# 1_P1_schdoc.net
KiCad netlist of a schematic drawn in Altium Designer
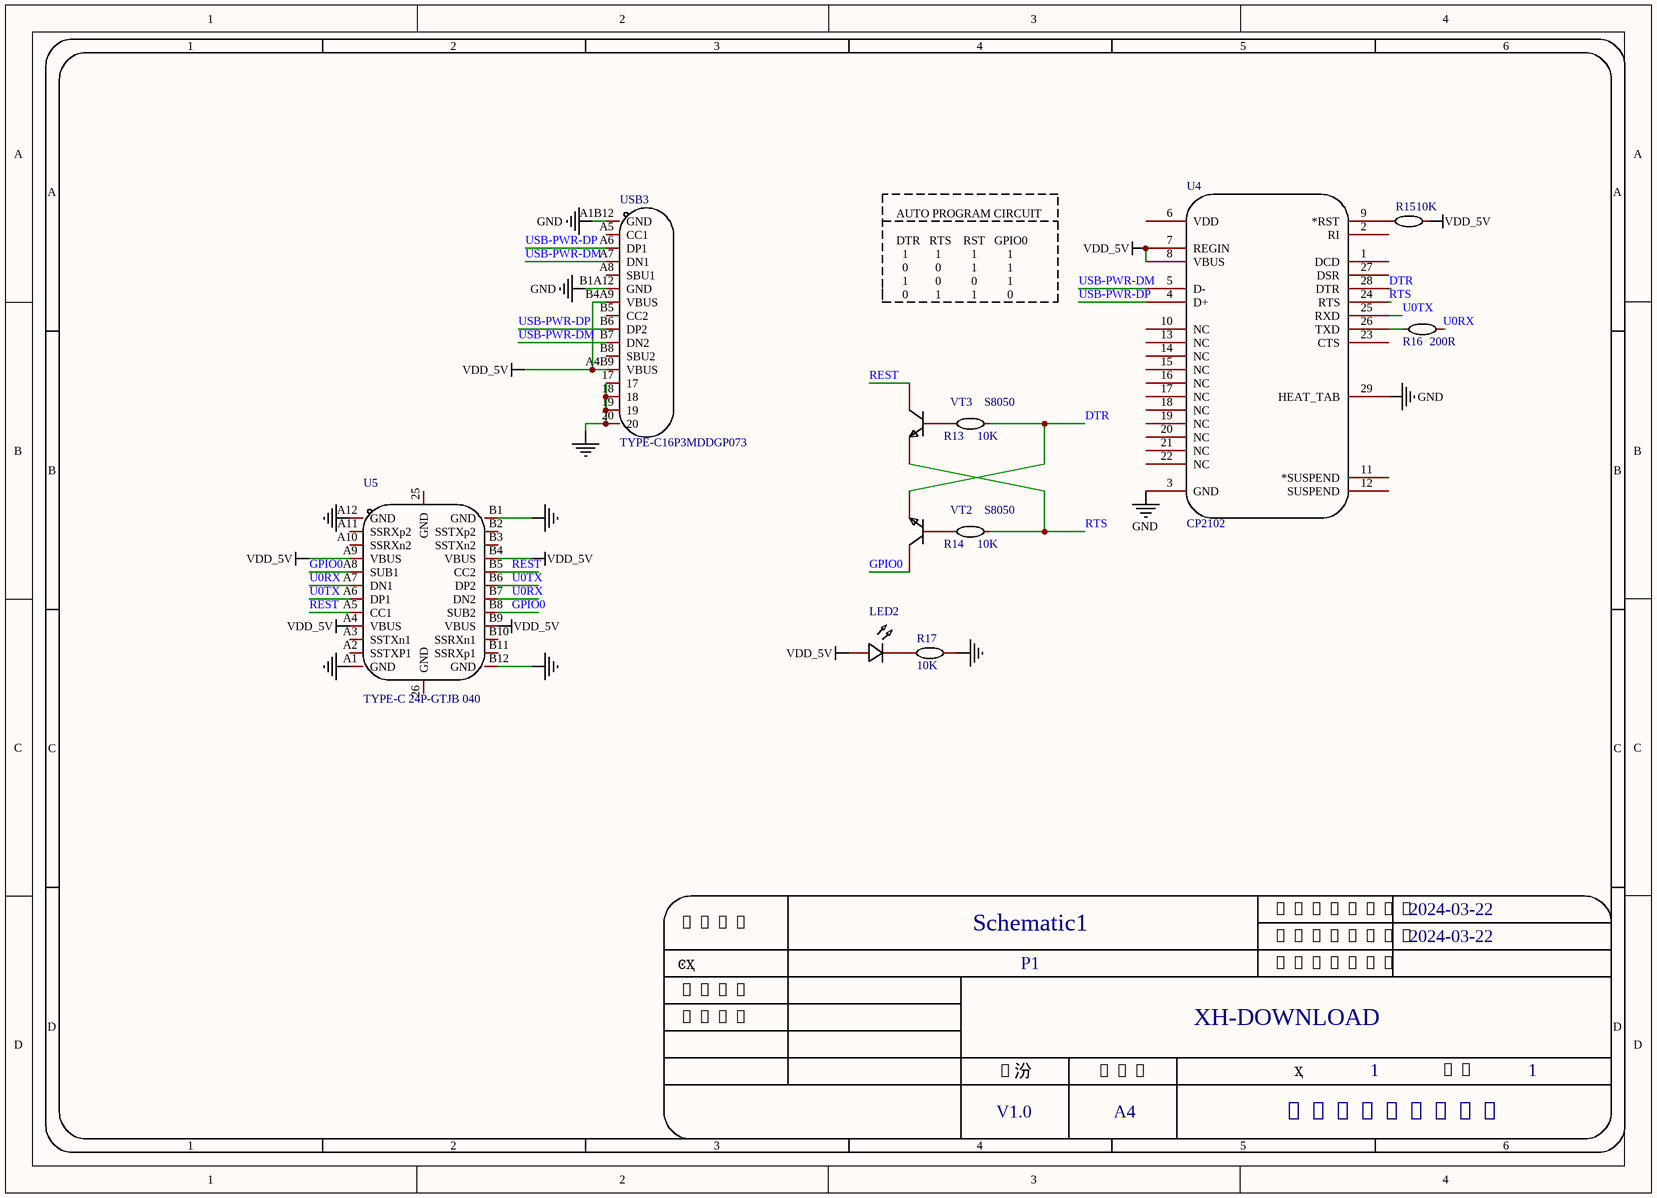
[diagram p0: 1_P1.schdoc.schdoc]

(export (version "E")
  (design (tool "Eeschema 10.0.6"))
  (components
    (comp (ref "LED2")
      (value "LED_0603-R")
      (footprint "LED_0603")
      (libsource (lib "altium-import") (part "root_0_LED_0603-R_"))
    )
    (comp (ref "R13")
      (value "10K")
      (footprint "C-0402")
      (description "Resistor")
      (fields (field (name "NAME") "10K"))
      (libsource (lib "altium-import") (part "root_2_12K_"))
    )
    (comp (ref "R14")
      (value "10K")
      (footprint "C-0402")
      (description "Resistor")
      (fields (field (name "NAME") "10K"))
      (libsource (lib "altium-import") (part "root_2_12K_"))
    )
    (comp (ref "R15")
      (value "10K")
      (footprint "C-0402")
      (description "Resistor")
      (fields (field (name "NAME") "10K"))
      (libsource (lib "altium-import") (part "root_2_10K_"))
    )
    (comp (ref "R16")
      (value "200R")
      (footprint "C-0402")
      (description "Resistor")
      (fields (field (name "NAME") "200R"))
      (libsource (lib "altium-import") (part "root_2_200R_"))
    )
    (comp (ref "R17")
      (value "10K")
      (footprint "R0603")
      (fields (field (name "NAME") "10K"))
      (libsource (lib "altium-import") (part "root_0_Res_0603_"))
    )
    (comp (ref "U4")
      (value "CP2102")
      (footprint "QFN28")
      (description "USB转TTL")
      (fields (field (name "NAME") "CP2102"))
      (libsource (lib "altium-import") (part "root_0_CP2102_"))
    )
    (comp (ref "U5")
      (value "TYPE-C 24P-GTJB 040")
      (footprint "USB-C-SMD_TYPE-C-24P-GTJB-040")
      (fields (field (name "NAME") "TYPE-C 24P-GTJB 040") (field (name "MANUFACTURER") "SHOU HAN(�׺�)"))
      (libsource (lib "altium-import") (part "root_0_TYPE-C 24P-GTJB 040_"))
    )
    (comp (ref "USB3")
      (value "TYPE-C16P3MDDGP073")
      (footprint "USB-SMD_TYPE-C16PIN-1")
      (fields (field (name "NAME") "TYPE-C16P3MDDGP073") (field (name "MANUFACTURER") "SHOU HAN(�׺�)"))
      (libsource (lib "altium-import") (part "root_0_TYPE-C16P3MDDGP073_"))
    )
    (comp (ref "VT2")
      (value "S8050")
      (footprint "SOT-233")
      (description "Surface mount NPN transistor, package SOT-23")
      (fields (field (name "NAME") "S8050"))
      (libsource (lib "altium-import") (part "root_2_S8050_"))
    )
    (comp (ref "VT3")
      (value "S8050")
      (footprint "SOT-233")
      (description "Surface mount NPN transistor, package SOT-23")
      (fields (field (name "NAME") "S8050"))
      (libsource (lib "altium-import") (part "root_0_mirrored_S8050_"))
    )
  )
  (nets
    (net (code "1") (name "/DTR") (class "Default")
      (node (ref "R13") (pin "1") (pinfunction "1_1") (pintype "passive"))
      (node (ref "U4") (pin "28") (pinfunction "DTR_28") (pintype "passive"))
      (node (ref "VT2") (pin "2") (pinfunction "E_2") (pintype "passive"))
    )
    (net (code "2") (name "/GPIO0") (class "Default")
      (node (ref "U5") (pin "A8") (pinfunction "SUB1_A8") (pintype "passive"))
      (node (ref "U5") (pin "B8") (pinfunction "SUB2_B8") (pintype "passive"))
      (node (ref "VT2") (pin "3") (pinfunction "C_3") (pintype "passive"))
    )
    (net (code "3") (name "/REST") (class "Default")
      (node (ref "U5") (pin "A5") (pinfunction "CC1_A5") (pintype "passive"))
      (node (ref "U5") (pin "B5") (pinfunction "CC2_B5") (pintype "passive"))
      (node (ref "VT3") (pin "3") (pinfunction "C_3") (pintype "passive"))
    )
    (net (code "4") (name "/RTS") (class "Default")
      (node (ref "R14") (pin "1") (pinfunction "1_1") (pintype "passive"))
      (node (ref "U4") (pin "24") (pinfunction "RTS_24") (pintype "passive"))
      (node (ref "VT3") (pin "2") (pinfunction "E_2") (pintype "passive"))
    )
    (net (code "5") (name "/U0RX") (class "Default")
      (node (ref "R16") (pin "1") (pinfunction "1_1") (pintype "passive"))
      (node (ref "U5") (pin "A7") (pinfunction "DN1_A7") (pintype "passive"))
      (node (ref "U5") (pin "B7") (pinfunction "DN2_B7") (pintype "passive"))
    )
    (net (code "6") (name "/U0TX") (class "Default")
      (node (ref "U4") (pin "25") (pinfunction "RXD_25") (pintype "passive"))
      (node (ref "U5") (pin "A6") (pinfunction "DP1_A6") (pintype "passive"))
      (node (ref "U5") (pin "B6") (pinfunction "DP2_B6") (pintype "passive"))
    )
    (net (code "7") (name "/USB-PWR-DM") (class "Default")
      (node (ref "U4") (pin "5") (pinfunction "D-_5") (pintype "passive"))
      (node (ref "USB3") (pin "A7") (pinfunction "DN1_A7") (pintype "passive"))
      (node (ref "USB3") (pin "B7") (pinfunction "DN2_B7") (pintype "passive"))
    )
    (net (code "8") (name "/USB-PWR-DP") (class "Default")
      (node (ref "U4") (pin "4") (pinfunction "D+_4") (pintype "passive"))
      (node (ref "USB3") (pin "A6") (pinfunction "DP1_A6") (pintype "passive"))
      (node (ref "USB3") (pin "B6") (pinfunction "DP2_B6") (pintype "passive"))
    )
    (net (code "9") (name "<NO NET>") (class "Default")
      (node (ref "R17") (pin "2") (pinfunction "2_2") (pintype "passive"))
      (node (ref "U5") (pin "A1") (pinfunction "GND_A1") (pintype "passive"))
      (node (ref "U5") (pin "A12") (pinfunction "GND_A12") (pintype "passive"))
      (node (ref "U5") (pin "B1") (pinfunction "GND_B1") (pintype "passive"))
      (node (ref "U5") (pin "B12") (pinfunction "GND_B12") (pintype "passive"))
    )
    (net (code "10") (name "GND") (class "Default")
      (node (ref "U4") (pin "29") (pinfunction "HEAT_TAB_29") (pintype "passive"))
      (node (ref "U4") (pin "3") (pinfunction "GND_3") (pintype "passive"))
      (node (ref "USB3") (pin "17") (pinfunction "17_17") (pintype "passive"))
      (node (ref "USB3") (pin "18") (pinfunction "18_18") (pintype "passive"))
      (node (ref "USB3") (pin "19") (pinfunction "19_19") (pintype "passive"))
      (node (ref "USB3") (pin "20") (pinfunction "20_20") (pintype "passive"))
      (node (ref "USB3") (pin "A1B12") (pinfunction "GND_A1B12") (pintype "passive"))
      (node (ref "USB3") (pin "B1A12") (pinfunction "GND_B1A12") (pintype "passive"))
    )
    (net (code "11") (name "Net-(LED2-C)") (class "Default")
      (node (ref "LED2") (pin "1") (pinfunction "C_1") (pintype "passive"))
      (node (ref "R17") (pin "1") (pinfunction "1_1") (pintype "passive"))
    )
    (net (code "12") (name "Net-(U4-*RST)") (class "Default")
      (node (ref "R15") (pin "2") (pinfunction "2_2") (pintype "passive"))
      (node (ref "U4") (pin "9") (pinfunction "*RST_9") (pintype "passive"))
    )
    (net (code "13") (name "Net-(U4-TXD)") (class "Default")
      (node (ref "R16") (pin "2") (pinfunction "2_2") (pintype "passive"))
      (node (ref "U4") (pin "26") (pinfunction "TXD_26") (pintype "passive"))
    )
    (net (code "14") (name "Net-(VT2-B)") (class "Default")
      (node (ref "R14") (pin "2") (pinfunction "2_2") (pintype "passive"))
      (node (ref "VT2") (pin "1") (pinfunction "B_1") (pintype "passive"))
    )
    (net (code "15") (name "Net-(VT3-B)") (class "Default")
      (node (ref "R13") (pin "2") (pinfunction "2_2") (pintype "passive"))
      (node (ref "VT3") (pin "1") (pinfunction "B_1") (pintype "passive"))
    )
    (net (code "16") (name "VDD_5V") (class "Default")
      (node (ref "LED2") (pin "2") (pinfunction "A_2") (pintype "passive"))
      (node (ref "R15") (pin "1") (pinfunction "1_1") (pintype "passive"))
      (node (ref "U4") (pin "7") (pinfunction "REGIN_7") (pintype "passive"))
      (node (ref "U4") (pin "8") (pinfunction "VBUS_8") (pintype "passive"))
      (node (ref "U5") (pin "A4") (pinfunction "VBUS_A4") (pintype "passive"))
      (node (ref "U5") (pin "A9") (pinfunction "VBUS_A9") (pintype "passive"))
      (node (ref "U5") (pin "B4") (pinfunction "VBUS_B4") (pintype "passive"))
      (node (ref "U5") (pin "B9") (pinfunction "VBUS_B9") (pintype "passive"))
      (node (ref "USB3") (pin "A4B9") (pinfunction "VBUS_A4B9") (pintype "passive"))
      (node (ref "USB3") (pin "B4A9") (pinfunction "VBUS_B4A9") (pintype "passive"))
    )
    (net (code "17") (name "unconnected-(U4-*SUSPEND-Pad11)") (class "Default")
      (node (ref "U4") (pin "11") (pinfunction "*SUSPEND_11") (pintype "passive"))
    )
    (net (code "18") (name "unconnected-(U4-CTS-Pad23)") (class "Default")
      (node (ref "U4") (pin "23") (pinfunction "CTS_23") (pintype "passive"))
    )
    (net (code "19") (name "unconnected-(U4-DCD-Pad1)") (class "Default")
      (node (ref "U4") (pin "1") (pinfunction "DCD_1") (pintype "passive"))
    )
    (net (code "20") (name "unconnected-(U4-DSR-Pad27)") (class "Default")
      (node (ref "U4") (pin "27") (pinfunction "DSR_27") (pintype "passive"))
    )
    (net (code "21") (name "unconnected-(U4-NC-Pad10)") (class "Default")
      (node (ref "U4") (pin "10") (pinfunction "NC_10") (pintype "passive"))
    )
    (net (code "22") (name "unconnected-(U4-NC-Pad13)") (class "Default")
      (node (ref "U4") (pin "13") (pinfunction "NC_13") (pintype "passive"))
    )
    (net (code "23") (name "unconnected-(U4-NC-Pad14)") (class "Default")
      (node (ref "U4") (pin "14") (pinfunction "NC_14") (pintype "passive"))
    )
    (net (code "24") (name "unconnected-(U4-NC-Pad15)") (class "Default")
      (node (ref "U4") (pin "15") (pinfunction "NC_15") (pintype "passive"))
    )
    (net (code "25") (name "unconnected-(U4-NC-Pad16)") (class "Default")
      (node (ref "U4") (pin "16") (pinfunction "NC_16") (pintype "passive"))
    )
    (net (code "26") (name "unconnected-(U4-NC-Pad17)") (class "Default")
      (node (ref "U4") (pin "17") (pinfunction "NC_17") (pintype "passive"))
    )
    (net (code "27") (name "unconnected-(U4-NC-Pad18)") (class "Default")
      (node (ref "U4") (pin "18") (pinfunction "NC_18") (pintype "passive"))
    )
    (net (code "28") (name "unconnected-(U4-NC-Pad19)") (class "Default")
      (node (ref "U4") (pin "19") (pinfunction "NC_19") (pintype "passive"))
    )
    (net (code "29") (name "unconnected-(U4-NC-Pad20)") (class "Default")
      (node (ref "U4") (pin "20") (pinfunction "NC_20") (pintype "passive"))
    )
    (net (code "30") (name "unconnected-(U4-NC-Pad21)") (class "Default")
      (node (ref "U4") (pin "21") (pinfunction "NC_21") (pintype "passive"))
    )
    (net (code "31") (name "unconnected-(U4-NC-Pad22)") (class "Default")
      (node (ref "U4") (pin "22") (pinfunction "NC_22") (pintype "passive"))
    )
    (net (code "32") (name "unconnected-(U4-RI-Pad2)") (class "Default")
      (node (ref "U4") (pin "2") (pinfunction "RI_2") (pintype "passive"))
    )
    (net (code "33") (name "unconnected-(U4-SUSPEND-Pad12)") (class "Default")
      (node (ref "U4") (pin "12") (pinfunction "SUSPEND_12") (pintype "passive"))
    )
    (net (code "34") (name "unconnected-(U4-VDD-Pad6)") (class "Default")
      (node (ref "U4") (pin "6") (pinfunction "VDD_6") (pintype "passive"))
    )
    (net (code "35") (name "unconnected-(U5-GND-Pad25)") (class "Default")
      (node (ref "U5") (pin "25") (pinfunction "GND_25") (pintype "passive"))
    )
    (net (code "36") (name "unconnected-(U5-GND-Pad26)") (class "Default")
      (node (ref "U5") (pin "26") (pinfunction "GND_26") (pintype "passive"))
    )
    (net (code "37") (name "unconnected-(U5-SSRXn1-PadB10)") (class "Default")
      (node (ref "U5") (pin "B10") (pinfunction "SSRXn1_B10") (pintype "passive"))
    )
    (net (code "38") (name "unconnected-(U5-SSRXn2-PadA10)") (class "Default")
      (node (ref "U5") (pin "A10") (pinfunction "SSRXn2_A10") (pintype "passive"))
    )
    (net (code "39") (name "unconnected-(U5-SSRXp1-PadB11)") (class "Default")
      (node (ref "U5") (pin "B11") (pinfunction "SSRXp1_B11") (pintype "passive"))
    )
    (net (code "40") (name "unconnected-(U5-SSRXp2-PadA11)") (class "Default")
      (node (ref "U5") (pin "A11") (pinfunction "SSRXp2_A11") (pintype "passive"))
    )
    (net (code "41") (name "unconnected-(U5-SSTXP1-PadA2)") (class "Default")
      (node (ref "U5") (pin "A2") (pinfunction "SSTXP1_A2") (pintype "passive"))
    )
    (net (code "42") (name "unconnected-(U5-SSTXn1-PadA3)") (class "Default")
      (node (ref "U5") (pin "A3") (pinfunction "SSTXn1_A3") (pintype "passive"))
    )
    (net (code "43") (name "unconnected-(U5-SSTXn2-PadB3)") (class "Default")
      (node (ref "U5") (pin "B3") (pinfunction "SSTXn2_B3") (pintype "passive"))
    )
    (net (code "44") (name "unconnected-(U5-SSTXp2-PadB2)") (class "Default")
      (node (ref "U5") (pin "B2") (pinfunction "SSTXp2_B2") (pintype "passive"))
    )
    (net (code "45") (name "unconnected-(USB3-CC1-PadA5)") (class "Default")
      (node (ref "USB3") (pin "A5") (pinfunction "CC1_A5") (pintype "passive"))
    )
    (net (code "46") (name "unconnected-(USB3-CC2-PadB5)") (class "Default")
      (node (ref "USB3") (pin "B5") (pinfunction "CC2_B5") (pintype "passive"))
    )
    (net (code "47") (name "unconnected-(USB3-SBU1-PadA8)") (class "Default")
      (node (ref "USB3") (pin "A8") (pinfunction "SBU1_A8") (pintype "passive"))
    )
    (net (code "48") (name "unconnected-(USB3-SBU2-PadB8)") (class "Default")
      (node (ref "USB3") (pin "B8") (pinfunction "SBU2_B8") (pintype "passive"))
    )
  )
)
